# LilyPad-Dev-v34.net
KiCad netlist of a schematic drawn in EAGLE
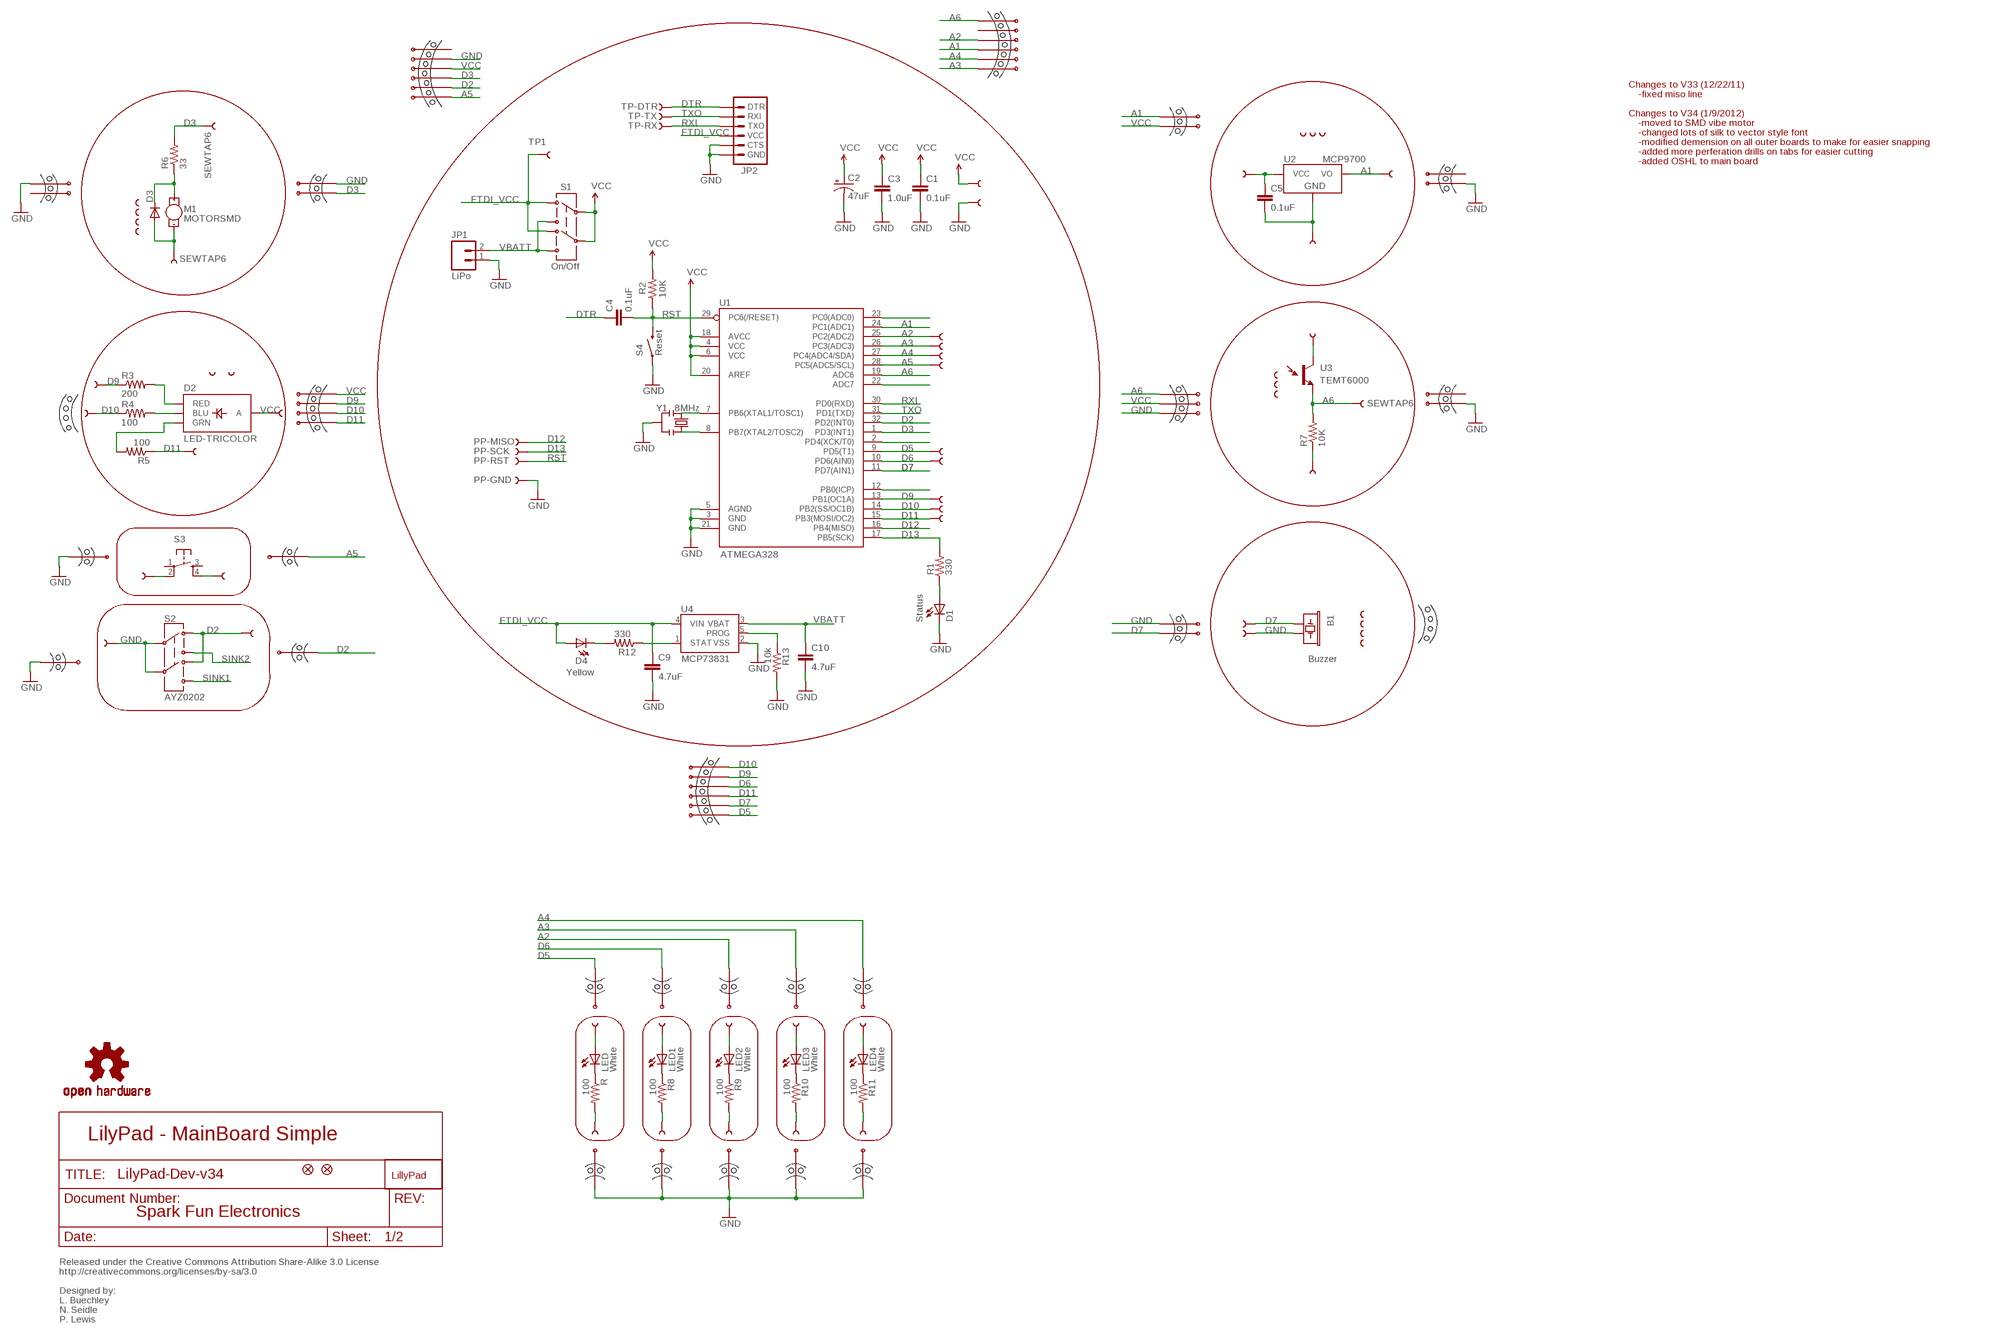
[diagram p0: schematic, sheet 1]
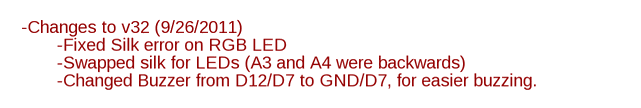
[diagram p1: schematic, sheet 2]

(export (version "E")
  (design (tool "Eeschema 10.0.6"))
  (components
    (comp (ref "1")
      (value "SEWTAP-NOHOLE2")
      (footprint "eagle-import:PETAL-NOHOLE-2SIDE")
      (libsource (lib "eagle-import") (part "SEWTAP-NOHOLE2"))
    )
    (comp (ref "2")
      (value "SEWTAP-NOHOLE2")
      (footprint "eagle-import:PETAL-NOHOLE-2SIDE")
      (libsource (lib "eagle-import") (part "SEWTAP-NOHOLE2"))
    )
    (comp (ref "3")
      (value "SEWTAP-NOHOLE2")
      (footprint "eagle-import:PETAL-NOHOLE-2SIDE")
      (libsource (lib "eagle-import") (part "SEWTAP-NOHOLE2"))
    )
    (comp (ref "4")
      (value "SEWTAP-NOHOLE2")
      (footprint "eagle-import:PETAL-NOHOLE-2SIDE")
      (libsource (lib "eagle-import") (part "SEWTAP-NOHOLE2"))
    )
    (comp (ref "A2/16")
      (value "SEWTAP9")
      (footprint "eagle-import:PETAL-LONG-1-2SIDE")
      (libsource (lib "eagle-import") (part "SEWTAP9"))
    )
    (comp (ref "A3/17")
      (value "SEWTAP9")
      (footprint "eagle-import:PETAL-LONG-1-2SIDE")
      (libsource (lib "eagle-import") (part "SEWTAP9"))
    )
    (comp (ref "A4/18")
      (value "SEWTAP9")
      (footprint "eagle-import:PETAL-LONG-1-2SIDE")
      (libsource (lib "eagle-import") (part "SEWTAP9"))
    )
    (comp (ref "A5/19")
      (value "SEWTAP9")
      (footprint "eagle-import:PETAL-LONG-1-2SIDE")
      (libsource (lib "eagle-import") (part "SEWTAP9"))
    )
    (comp (ref "B1")
      (value "Buzzer")
      (footprint "eagle-import:BUZZER-CCV")
      (libsource (lib "eagle-import") (part "BUZZERSMD2"))
    )
    (comp (ref "BUTTON-")
      (value "SEWTAP8")
      (footprint "eagle-import:PETAL-SMALL")
      (libsource (lib "eagle-import") (part "SEWTAP4"))
    )
    (comp (ref "BUTTONS")
      (value "SEWTAP8")
      (footprint "eagle-import:PETAL-SMALL")
      (libsource (lib "eagle-import") (part "SEWTAP4"))
    )
    (comp (ref "C1")
      (value "0.1uF")
      (footprint "eagle-import:0402-CAP")
      (libsource (lib "eagle-import") (part "CAP0402-CAP"))
    )
    (comp (ref "C2")
      (value "47uF")
      (footprint "eagle-import:EIA3528")
      (libsource (lib "eagle-import") (part "CAP_POL3528"))
    )
    (comp (ref "C3")
      (value "1.0uF")
      (footprint "eagle-import:0402-CAP")
      (libsource (lib "eagle-import") (part "CAP0402-CAP"))
    )
    (comp (ref "C4")
      (value "0.1uF")
      (footprint "eagle-import:0402-CAP")
      (libsource (lib "eagle-import") (part "CAP0402-CAP"))
    )
    (comp (ref "C5")
      (value "0.1uF")
      (footprint "eagle-import:0603-CAP")
      (libsource (lib "eagle-import") (part "CAP0603-CAP"))
    )
    (comp (ref "C9")
      (value "4.7uF")
      (footprint "eagle-import:0402-CAP")
      (libsource (lib "eagle-import") (part "CAP0402-CAP"))
    )
    (comp (ref "C10")
      (value "4.7uF")
      (footprint "eagle-import:0402-CAP")
      (libsource (lib "eagle-import") (part "CAP0402-CAP"))
    )
    (comp (ref "D1")
      (value "Status")
      (footprint "eagle-import:LED-0603")
      (libsource (lib "eagle-import") (part "LED0603"))
    )
    (comp (ref "D2")
      (value "LED-TRICOLOR")
      (footprint "eagle-import:LED-TRICOLOR-SMD")
      (libsource (lib "eagle-import") (part "LED-TRICOLOR"))
    )
    (comp (ref "D3")
      (value "DIODESOD")
      (footprint "eagle-import:SOD-323")
      (libsource (lib "eagle-import") (part "DIODESOD"))
    )
    (comp (ref "D4")
      (value "Yellow")
      (footprint "eagle-import:LED-0603")
      (libsource (lib "eagle-import") (part "LED0603"))
    )
    (comp (ref "JP1")
      (value "LiPo")
      (footprint "eagle-import:JST-2-SMD")
      (libsource (lib "eagle-import") (part "M02-JST-2MM-SMT"))
    )
    (comp (ref "JP2")
      (value "ARDUINO_SERIAL_PROGRAMSMD")
      (footprint "eagle-import:1X06-SMD")
      (libsource (lib "eagle-import") (part "ARDUINO_SERIAL_PROGRAMSMD"))
    )
    (comp (ref "JP3")
      (value "FIDUCIAL1X2")
      (footprint "eagle-import:FIDUCIAL-1X2")
      (libsource (lib "eagle-import") (part "FIDUCIAL1X2"))
    )
    (comp (ref "JP4")
      (value "FIDUCIAL1X2")
      (footprint "eagle-import:FIDUCIAL-1X2")
      (libsource (lib "eagle-import") (part "FIDUCIAL1X2"))
    )
    (comp (ref "LED")
      (value "White")
      (footprint "eagle-import:LED-1206")
      (libsource (lib "eagle-import") (part "SparkFun-3-2-07_LED1206"))
    )
    (comp (ref "LED+")
      (value "SEWTAP6")
      (footprint "eagle-import:PETAL-SMALL-2SIDE")
      (libsource (lib "eagle-import") (part "SEWTAP6"))
    )
    (comp (ref "LED+1")
      (value "SEWTAP6")
      (footprint "eagle-import:PETAL-SMALL-2SIDE")
      (libsource (lib "eagle-import") (part "SEWTAP6"))
    )
    (comp (ref "LED+2")
      (value "SEWTAP6")
      (footprint "eagle-import:PETAL-SMALL-2SIDE")
      (libsource (lib "eagle-import") (part "SEWTAP6"))
    )
    (comp (ref "LED+3")
      (value "SEWTAP6")
      (footprint "eagle-import:PETAL-SMALL-2SIDE")
      (libsource (lib "eagle-import") (part "SEWTAP6"))
    )
    (comp (ref "LED+4")
      (value "SEWTAP6")
      (footprint "eagle-import:PETAL-SMALL-2SIDE")
      (libsource (lib "eagle-import") (part "SEWTAP6"))
    )
    (comp (ref "LED-")
      (value "SEWTAP6")
      (footprint "eagle-import:PETAL-SMALL-2SIDE")
      (libsource (lib "eagle-import") (part "SEWTAP6"))
    )
    (comp (ref "LED-1")
      (value "SEWTAP6")
      (footprint "eagle-import:PETAL-SMALL-2SIDE")
      (libsource (lib "eagle-import") (part "SEWTAP6"))
    )
    (comp (ref "LED-2")
      (value "SEWTAP6")
      (footprint "eagle-import:PETAL-SMALL-2SIDE")
      (libsource (lib "eagle-import") (part "SEWTAP6"))
    )
    (comp (ref "LED-3")
      (value "SEWTAP6")
      (footprint "eagle-import:PETAL-SMALL-2SIDE")
      (libsource (lib "eagle-import") (part "SEWTAP6"))
    )
    (comp (ref "LED-4")
      (value "SEWTAP6")
      (footprint "eagle-import:PETAL-SMALL-2SIDE")
      (libsource (lib "eagle-import") (part "SEWTAP6"))
    )
    (comp (ref "LED1")
      (value "White")
      (footprint "eagle-import:LED-1206")
      (libsource (lib "eagle-import") (part "SparkFun-3-2-07_LED1206"))
    )
    (comp (ref "LED2")
      (value "White")
      (footprint "eagle-import:LED-1206")
      (libsource (lib "eagle-import") (part "SparkFun-3-2-07_LED1206"))
    )
    (comp (ref "LED3")
      (value "White")
      (footprint "eagle-import:LED-1206")
      (libsource (lib "eagle-import") (part "SparkFun-3-2-07_LED1206"))
    )
    (comp (ref "LED4")
      (value "White")
      (footprint "eagle-import:LED-1206")
      (libsource (lib "eagle-import") (part "SparkFun-3-2-07_LED1206"))
    )
    (comp (ref "LIGHT+")
      (value "SEWTAP6")
      (footprint "eagle-import:PETAL-SMALL")
      (libsource (lib "eagle-import") (part "SEWTAP4"))
    )
    (comp (ref "LIGHT-")
      (value "SEWTAP6")
      (footprint "eagle-import:PETAL-SMALL")
      (libsource (lib "eagle-import") (part "SEWTAP4"))
    )
    (comp (ref "LIGHT1")
      (value "SEWTAP-NOHOLE2")
      (footprint "eagle-import:PETAL-NOHOLE-2SIDE")
      (libsource (lib "eagle-import") (part "SEWTAP-NOHOLE2"))
    )
    (comp (ref "LIGHT2")
      (value "SEWTAP-NOHOLE2")
      (footprint "eagle-import:PETAL-NOHOLE-2SIDE")
      (libsource (lib "eagle-import") (part "SEWTAP-NOHOLE2"))
    )
    (comp (ref "LIGHT3")
      (value "SEWTAP-NOHOLE2")
      (footprint "eagle-import:PETAL-NOHOLE-2SIDE")
      (libsource (lib "eagle-import") (part "SEWTAP-NOHOLE2"))
    )
    (comp (ref "LIGHTS")
      (value "SEWTAP6")
      (footprint "eagle-import:PETAL-SMALL")
      (libsource (lib "eagle-import") (part "SEWTAP4"))
    )
    (comp (ref "LOGO")
      (value "LOGO-LPLPA")
      (footprint "eagle-import:LOGO-LPA")
      (libsource (lib "eagle-import") (part "LOGO-LPLPA"))
    )
    (comp (ref "M1")
      (value "MOTORSMD")
      (footprint "eagle-import:VIBE-MOTOR-10MM-SMD")
      (libsource (lib "eagle-import") (part "MOTORSMD"))
    )
    (comp (ref "PP-GND")
      (value "TEST-POINT3X5")
      (footprint "eagle-import:PAD.03X.05")
      (libsource (lib "eagle-import") (part "TEST-POINT3X5"))
    )
    (comp (ref "PP-MISO")
      (value "TEST-POINT3X5")
      (footprint "eagle-import:PAD.03X.05")
      (libsource (lib "eagle-import") (part "TEST-POINT3X5"))
    )
    (comp (ref "PP-RST")
      (value "TEST-POINT3X5")
      (footprint "eagle-import:PAD.03X.05")
      (libsource (lib "eagle-import") (part "TEST-POINT3X5"))
    )
    (comp (ref "PP-SCK")
      (value "TEST-POINT3X5")
      (footprint "eagle-import:PAD.03X.05")
      (libsource (lib "eagle-import") (part "TEST-POINT3X5"))
    )
    (comp (ref "R")
      (value "100")
      (footprint "eagle-import:0603-RES")
      (libsource (lib "eagle-import") (part "RESISTOR0603-RES"))
    )
    (comp (ref "R1")
      (value "330")
      (footprint "eagle-import:0402-RES")
      (libsource (lib "eagle-import") (part "RESISTOR0402-RES"))
    )
    (comp (ref "R2")
      (value "10K")
      (footprint "eagle-import:0402-RES")
      (libsource (lib "eagle-import") (part "RESISTOR0402-RES"))
    )
    (comp (ref "R3")
      (value "200")
      (footprint "eagle-import:0402-RES")
      (libsource (lib "eagle-import") (part "RESISTOR0402-RES"))
    )
    (comp (ref "R4")
      (value "100")
      (footprint "eagle-import:0402-RES")
      (libsource (lib "eagle-import") (part "RESISTOR0402-RES"))
    )
    (comp (ref "R5")
      (value "100")
      (footprint "eagle-import:0402-RES")
      (libsource (lib "eagle-import") (part "RESISTOR0402-RES"))
    )
    (comp (ref "R6")
      (value "33")
      (footprint "eagle-import:0402-RES")
      (libsource (lib "eagle-import") (part "RESISTOR0402-RES"))
    )
    (comp (ref "R7")
      (value "10K")
      (footprint "eagle-import:0402-RES")
      (libsource (lib "eagle-import") (part "RESISTOR0402-RES"))
    )
    (comp (ref "R8")
      (value "100")
      (footprint "eagle-import:0603-RES")
      (libsource (lib "eagle-import") (part "RESISTOR0603-RES"))
    )
    (comp (ref "R9")
      (value "100")
      (footprint "eagle-import:0603-RES")
      (libsource (lib "eagle-import") (part "RESISTOR0603-RES"))
    )
    (comp (ref "R10")
      (value "100")
      (footprint "eagle-import:0603-RES")
      (libsource (lib "eagle-import") (part "RESISTOR0603-RES"))
    )
    (comp (ref "R11")
      (value "100")
      (footprint "eagle-import:0603-RES")
      (libsource (lib "eagle-import") (part "RESISTOR0603-RES"))
    )
    (comp (ref "R12")
      (value "330")
      (footprint "eagle-import:0402-RES")
      (libsource (lib "eagle-import") (part "RESISTOR0402-RES"))
    )
    (comp (ref "R13")
      (value "10k")
      (footprint "eagle-import:0402-RES")
      (libsource (lib "eagle-import") (part "RESISTOR0402-RES"))
    )
    (comp (ref "S1")
      (value "On/Off")
      (footprint "eagle-import:AYZ0202")
      (libsource (lib "eagle-import") (part "AYZ0202"))
    )
    (comp (ref "S2")
      (value "AYZ0202")
      (footprint "eagle-import:AYZ0202")
      (libsource (lib "eagle-import") (part "AYZ0202"))
    )
    (comp (ref "S3")
      (value "TAC_SWITCHSMD")
      (footprint "eagle-import:TACTILE_SWITCH_SMD")
      (libsource (lib "eagle-import") (part "TAC_SWITCHSMD"))
    )
    (comp (ref "S4")
      (value "Reset")
      (footprint "eagle-import:TACTILE_SWITCH_SMD")
      (libsource (lib "eagle-import") (part "SWITCH-MOMENTARY-2SMD"))
    )
    (comp (ref "SLIDEOFF")
      (value "SEWTAP8")
      (footprint "eagle-import:PETAL-SMALL")
      (libsource (lib "eagle-import") (part "SEWTAP4"))
    )
    (comp (ref "SLIDEON")
      (value "SEWTAP8")
      (footprint "eagle-import:PETAL-SMALL")
      (libsource (lib "eagle-import") (part "SEWTAP4"))
    )
    (comp (ref "TEMP+")
      (value "SEWTAP6")
      (footprint "eagle-import:PETAL-SMALL")
      (libsource (lib "eagle-import") (part "SEWTAP4"))
    )
    (comp (ref "TEMP-")
      (value "SEWTAP6")
      (footprint "eagle-import:PETAL-SMALL")
      (libsource (lib "eagle-import") (part "SEWTAP4"))
    )
    (comp (ref "TEMP1")
      (value "SEWTAP-NOHOLE2")
      (footprint "eagle-import:PETAL-NOHOLE-2SIDE")
      (libsource (lib "eagle-import") (part "SEWTAP-NOHOLE2"))
    )
    (comp (ref "TEMP2")
      (value "SEWTAP-NOHOLE2")
      (footprint "eagle-import:PETAL-NOHOLE-2SIDE")
      (libsource (lib "eagle-import") (part "SEWTAP-NOHOLE2"))
    )
    (comp (ref "TEMP3")
      (value "SEWTAP-NOHOLE2")
      (footprint "eagle-import:PETAL-NOHOLE-2SIDE")
      (libsource (lib "eagle-import") (part "SEWTAP-NOHOLE2"))
    )
    (comp (ref "TEMPS")
      (value "SEWTAP6")
      (footprint "eagle-import:PETAL-SMALL")
      (libsource (lib "eagle-import") (part "SEWTAP4"))
    )
    (comp (ref "TP-DTR")
      (value "TEST-POINT3X5")
      (footprint "eagle-import:PAD.03X.05")
      (libsource (lib "eagle-import") (part "TEST-POINT3X5"))
    )
    (comp (ref "TP-RX")
      (value "TEST-POINT3X5")
      (footprint "eagle-import:PAD.03X.05")
      (libsource (lib "eagle-import") (part "TEST-POINT3X5"))
    )
    (comp (ref "TP-TX")
      (value "TEST-POINT3X5")
      (footprint "eagle-import:PAD.03X.05")
      (libsource (lib "eagle-import") (part "TEST-POINT3X5"))
    )
    (comp (ref "TP1")
      (value "TEST-POINT3X5")
      (footprint "eagle-import:PAD.03X.05")
      (libsource (lib "eagle-import") (part "TEST-POINT3X5"))
    )
    (comp (ref "U$1")
      (value "SEWTAP9")
      (footprint "eagle-import:PETAL-LONG-1-2SIDE")
      (libsource (lib "eagle-import") (part "SEWTAP9"))
    )
    (comp (ref "U$2")
      (value "MOUSE-BITE-2")
      (footprint "eagle-import:MOUSE-BITE-2")
      (libsource (lib "eagle-import") (part "MOUSE-BITE-2"))
    )
    (comp (ref "U$3")
      (value "MOUSE-BITE-2")
      (footprint "eagle-import:MOUSE-BITE-2")
      (libsource (lib "eagle-import") (part "MOUSE-BITE-2"))
    )
    (comp (ref "U$4")
      (value "SEWTAP9")
      (footprint "eagle-import:PETAL-LONG-1-2SIDE")
      (libsource (lib "eagle-import") (part "SEWTAP9"))
    )
    (comp (ref "U$5")
      (value "MOUSE-BITE-2")
      (footprint "eagle-import:MOUSE-BITE-2")
      (libsource (lib "eagle-import") (part "MOUSE-BITE-2"))
    )
    (comp (ref "U$6")
      (value "MOUSE-BITE-2")
      (footprint "eagle-import:MOUSE-BITE-2")
      (libsource (lib "eagle-import") (part "MOUSE-BITE-2"))
    )
    (comp (ref "U$7")
      (value "MOUSE-BITE-66")
      (footprint "eagle-import:MOUSE-BITE-6")
      (libsource (lib "eagle-import") (part "MOUSE-BITE-66"))
    )
    (comp (ref "U$8")
      (value "MOUSE-BITE-66")
      (footprint "eagle-import:MOUSE-BITE-6")
      (libsource (lib "eagle-import") (part "MOUSE-BITE-66"))
    )
    (comp (ref "U$10")
      (value "MOUSE-BITE-12_HOLES")
      (footprint "eagle-import:MOUST-BITE-1-(2_HOLES)")
      (libsource (lib "eagle-import") (part "MOUSE-BITE-12_HOLES"))
    )
    (comp (ref "U$11")
      (value "MOUSE-BITE-12_HOLES")
      (footprint "eagle-import:MOUST-BITE-1-(2_HOLES)")
      (libsource (lib "eagle-import") (part "MOUSE-BITE-12_HOLES"))
    )
    (comp (ref "U$12")
      (value "MOUSE-BITE-12_HOLES")
      (footprint "eagle-import:MOUST-BITE-1-(2_HOLES)")
      (libsource (lib "eagle-import") (part "MOUSE-BITE-12_HOLES"))
    )
    (comp (ref "U$13")
      (value "MOUSE-BITE-12_HOLES")
      (footprint "eagle-import:MOUST-BITE-1-(2_HOLES)")
      (libsource (lib "eagle-import") (part "MOUSE-BITE-12_HOLES"))
    )
    (comp (ref "U$14")
      (value "MOUSE-BITE-12_HOLES")
      (footprint "eagle-import:MOUST-BITE-1-(2_HOLES)")
      (libsource (lib "eagle-import") (part "MOUSE-BITE-12_HOLES"))
    )
    (comp (ref "U$15")
      (value "MOUSE-BITE-12_HOLES")
      (footprint "eagle-import:MOUST-BITE-1-(2_HOLES)")
      (libsource (lib "eagle-import") (part "MOUSE-BITE-12_HOLES"))
    )
    (comp (ref "U$16")
      (value "MOUSE-BITE-12_HOLES")
      (footprint "eagle-import:MOUST-BITE-1-(2_HOLES)")
      (libsource (lib "eagle-import") (part "MOUSE-BITE-12_HOLES"))
    )
    (comp (ref "U$17")
      (value "MOUSE-BITE-12_HOLES")
      (footprint "eagle-import:MOUST-BITE-1-(2_HOLES)")
      (libsource (lib "eagle-import") (part "MOUSE-BITE-12_HOLES"))
    )
    (comp (ref "U$18")
      (value "MOUSE-BITE-12_HOLES")
      (footprint "eagle-import:MOUST-BITE-1-(2_HOLES)")
      (libsource (lib "eagle-import") (part "MOUSE-BITE-12_HOLES"))
    )
    (comp (ref "U$19")
      (value "MOUSE-BITE-12_HOLES")
      (footprint "eagle-import:MOUST-BITE-1-(2_HOLES)")
      (libsource (lib "eagle-import") (part "MOUSE-BITE-12_HOLES"))
    )
    (comp (ref "U$20")
      (value "MOUSE-BITE-4")
      (footprint "eagle-import:MOUSE-BITE-4")
      (libsource (lib "eagle-import") (part "MOUSE-BITE-4"))
    )
    (comp (ref "U$22")
      (value "SEWTAP6")
      (footprint "eagle-import:PETAL-SMALL-2SIDE")
      (libsource (lib "eagle-import") (part "SEWTAP6"))
    )
    (comp (ref "U$23")
      (value "SEWTAP6")
      (footprint "eagle-import:PETAL-SMALL-2SIDE")
      (libsource (lib "eagle-import") (part "SEWTAP6"))
    )
    (comp (ref "U$24")
      (value "SEWTAP6")
      (footprint "eagle-import:PETAL-SMALL-2SIDE")
      (libsource (lib "eagle-import") (part "SEWTAP6"))
    )
    (comp (ref "U$25")
      (value "SEWTAP6")
      (footprint "eagle-import:PETAL-SMALL-2SIDE")
      (libsource (lib "eagle-import") (part "SEWTAP6"))
    )
    (comp (ref "U$26")
      (value "SEWTAP-NOHOLE2")
      (footprint "eagle-import:PETAL-NOHOLE-2SIDE")
      (libsource (lib "eagle-import") (part "SEWTAP-NOHOLE2"))
    )
    (comp (ref "U$27")
      (value "SEWTAP-NOHOLE2")
      (footprint "eagle-import:PETAL-NOHOLE-2SIDE")
      (libsource (lib "eagle-import") (part "SEWTAP-NOHOLE2"))
    )
    (comp (ref "U$32")
      (value "MOUSE-BITE-2")
      (footprint "eagle-import:MOUSE-BITE-2")
      (libsource (lib "eagle-import") (part "MOUSE-BITE-2"))
    )
    (comp (ref "U$32-")
      (value "SEWTAP6")
      (footprint "eagle-import:PETAL-SMALL")
      (libsource (lib "eagle-import") (part "SEWTAP4"))
    )
    (comp (ref "U$33")
      (value "MOUSE-BITE-3")
      (footprint "eagle-import:MOUSE-BITE-3")
      (libsource (lib "eagle-import") (part "MOUSE-BITE-3"))
    )
    (comp (ref "U$33+")
      (value "SEWTAP6")
      (footprint "eagle-import:PETAL-SMALL")
      (libsource (lib "eagle-import") (part "SEWTAP4"))
    )
    (comp (ref "U$37")
      (value "SEWTAP9")
      (footprint "eagle-import:PETAL-LONG-1-2SIDE")
      (libsource (lib "eagle-import") (part "SEWTAP9"))
    )
    (comp (ref "U$39")
      (value "SEWTAP9")
      (footprint "eagle-import:PETAL-LONG-1-2SIDE")
      (libsource (lib "eagle-import") (part "SEWTAP9"))
    )
    (comp (ref "U$40")
      (value "MOUSE-BITE-12_HOLES")
      (footprint "eagle-import:MOUST-BITE-1-(2_HOLES)")
      (libsource (lib "eagle-import") (part "MOUSE-BITE-12_HOLES"))
    )
    (comp (ref "U$41")
      (value "SEWTAP9")
      (footprint "eagle-import:PETAL-LONG-1-2SIDE")
      (libsource (lib "eagle-import") (part "SEWTAP9"))
    )
    (comp (ref "U$42")
      (value "MOUSE-BITE-12_HOLES")
      (footprint "eagle-import:MOUST-BITE-1-(2_HOLES)")
      (libsource (lib "eagle-import") (part "MOUSE-BITE-12_HOLES"))
    )
    (comp (ref "U$43")
      (value "SEWTAP9")
      (footprint "eagle-import:PETAL-LONG-1-2SIDE")
      (libsource (lib "eagle-import") (part "SEWTAP9"))
    )
    (comp (ref "U$44")
      (value "MOUSE-BITE-12_HOLES")
      (footprint "eagle-import:MOUST-BITE-1-(2_HOLES)")
      (libsource (lib "eagle-import") (part "MOUSE-BITE-12_HOLES"))
    )
    (comp (ref "U$45")
      (value "SEWTAP9")
      (footprint "eagle-import:PETAL-LONG-1-2SIDE")
      (libsource (lib "eagle-import") (part "SEWTAP9"))
    )
    (comp (ref "U$46")
      (value "MOUSE-BITE-12_HOLES")
      (footprint "eagle-import:MOUST-BITE-1-(2_HOLES)")
      (libsource (lib "eagle-import") (part "MOUSE-BITE-12_HOLES"))
    )
    (comp (ref "U$47")
      (value "MOUSE-BITE-2")
      (footprint "eagle-import:MOUSE-BITE-2")
      (libsource (lib "eagle-import") (part "MOUSE-BITE-2"))
    )
    (comp (ref "U$48")
      (value "MOUSE-BITE-3(NO_PADS)")
      (footprint "eagle-import:MOUSE-BITE-3(NO_PADS)")
      (libsource (lib "eagle-import") (part "MOUSE-BITE-3(NO_PADS)"))
    )
    (comp (ref "U$49")
      (value "MOUSE-BITE-3(NO_PADS)")
      (footprint "eagle-import:MOUSE-BITE-3(NO_PADS)")
      (libsource (lib "eagle-import") (part "MOUSE-BITE-3(NO_PADS)"))
    )
    (comp (ref "U$51")
      (value "MOUSE-BITE-66")
      (footprint "eagle-import:MOUSE-BITE-6")
      (libsource (lib "eagle-import") (part "MOUSE-BITE-66"))
    )
    (comp (ref "U$52")
      (value "OSHW-LOGOS")
      (footprint "eagle-import:OSHW-LOGO-S")
      (libsource (lib "eagle-import") (part "OSHW-LOGOS"))
    )
    (comp (ref "U1")
      (value "ATMEGA328")
      (footprint "eagle-import:TQFP32-08")
      (libsource (lib "eagle-import") (part "ATMEGA168"))
    )
    (comp (ref "U2")
      (value "MCP9700")
      (footprint "eagle-import:SOT23-3")
      (libsource (lib "eagle-import") (part "MCP9700SMD"))
    )
    (comp (ref "U3")
      (value "TEMT6000")
      (footprint "eagle-import:TEMT6000-SEN")
      (libsource (lib "eagle-import") (part "TEMT6000"))
    )
    (comp (ref "U4")
      (value "MCP73831")
      (footprint "eagle-import:SOT23-5")
      (libsource (lib "eagle-import") (part "MCP73831"))
    )
    (comp (ref "VIBE+")
      (value "SEWTAP6")
      (footprint "eagle-import:PETAL-SMALL")
      (libsource (lib "eagle-import") (part "SEWTAP4"))
    )
    (comp (ref "VIBE-")
      (value "SEWTAP6")
      (footprint "eagle-import:PETAL-SMALL")
      (libsource (lib "eagle-import") (part "SEWTAP4"))
    )
    (comp (ref "VIBE1")
      (value "SEWTAP-NOHOLE2")
      (footprint "eagle-import:PETAL-NOHOLE-2SIDE")
      (libsource (lib "eagle-import") (part "SEWTAP-NOHOLE2"))
    )
    (comp (ref "VIBE2")
      (value "SEWTAP-NOHOLE2")
      (footprint "eagle-import:PETAL-NOHOLE-2SIDE")
      (libsource (lib "eagle-import") (part "SEWTAP-NOHOLE2"))
    )
    (comp (ref "VIBE3")
      (value "SEWTAP-NOHOLE2")
      (footprint "eagle-import:PETAL-NOHOLE-2SIDE")
      (libsource (lib "eagle-import") (part "SEWTAP-NOHOLE2"))
    )
    (comp (ref "VIBE4")
      (value "SEWTAP-NOHOLE2")
      (footprint "eagle-import:PETAL-NOHOLE-2SIDE")
      (libsource (lib "eagle-import") (part "SEWTAP-NOHOLE2"))
    )
    (comp (ref "Y1")
      (value "8MHz")
      (footprint "eagle-import:RESONATOR-SMD")
      (libsource (lib "eagle-import") (part "RESONATORSMD"))
    )
  )
  (nets
    (net (code "1") (name "A1") (class "Default")
      (node (ref "TEMPS") (pin "1") (pinfunction "1_1") (pintype "bidirectional"))
      (node (ref "U$2") (pin "P$1") (pinfunction "P$1_P$1") (pintype "bidirectional"))
      (node (ref "U$7") (pin "P$4") (pinfunction "P$4_P$4") (pintype "bidirectional"))
      (node (ref "U1") (pin "24") (pinfunction "PC1(ADC1)_24") (pintype "bidirectional"))
      (node (ref "U2") (pin "2") (pinfunction "VO_2") (pintype "bidirectional"))
    )
    (net (code "2") (name "A2") (class "Default")
      (node (ref "A2/16") (pin "1") (pinfunction "1_1") (pintype "bidirectional"))
      (node (ref "U$12") (pin "P$1") (pinfunction "P$1_P$1") (pintype "bidirectional"))
      (node (ref "U$7") (pin "P$3") (pinfunction "P$3_P$3") (pintype "bidirectional"))
      (node (ref "U1") (pin "25") (pinfunction "PC2(ADC2)_25") (pintype "bidirectional"))
    )
    (net (code "3") (name "A3") (class "Default")
      (node (ref "A3/17") (pin "1") (pinfunction "1_1") (pintype "bidirectional"))
      (node (ref "U$13") (pin "P$1") (pinfunction "P$1_P$1") (pintype "bidirectional"))
      (node (ref "U$7") (pin "P$6") (pinfunction "P$6_P$6") (pintype "bidirectional"))
      (node (ref "U1") (pin "26") (pinfunction "PC3(ADC3)_26") (pintype "bidirectional"))
    )
    (net (code "4") (name "A4") (class "Default")
      (node (ref "A4/18") (pin "1") (pinfunction "1_1") (pintype "bidirectional"))
      (node (ref "U$14") (pin "P$1") (pinfunction "P$1_P$1") (pintype "bidirectional"))
      (node (ref "U$7") (pin "P$5") (pinfunction "P$5_P$5") (pintype "bidirectional"))
      (node (ref "U1") (pin "27") (pinfunction "PC4(ADC4/SDA)_27") (pintype "bidirectional"))
    )
    (net (code "5") (name "A5") (class "Default")
      (node (ref "A5/19") (pin "1") (pinfunction "1_1") (pintype "bidirectional"))
      (node (ref "BUTTONS") (pin "1") (pinfunction "1_1") (pintype "bidirectional"))
      (node (ref "S3") (pin "2") (pinfunction "2_2") (pintype "passive"))
      (node (ref "U$40") (pin "P$1") (pinfunction "P$1_P$1") (pintype "bidirectional"))
      (node (ref "U$8") (pin "P$1") (pinfunction "P$1_P$1") (pintype "bidirectional"))
      (node (ref "U1") (pin "28") (pinfunction "PC5(ADC5/SCL)_28") (pintype "bidirectional"))
    )
    (net (code "6") (name "A6") (class "Default")
      (node (ref "LIGHTS") (pin "1") (pinfunction "1_1") (pintype "bidirectional"))
      (node (ref "R7") (pin "2") (pinfunction "2_2") (pintype "passive"))
      (node (ref "U$33") (pin "P$1") (pinfunction "P$1_P$1") (pintype "bidirectional"))
      (node (ref "U$7") (pin "P$1") (pinfunction "P$1_P$1") (pintype "bidirectional"))
      (node (ref "U1") (pin "19") (pinfunction "ADC6_19") (pintype "bidirectional"))
      (node (ref "U3") (pin "EMITTER") (pinfunction "E1_EMITTER") (pintype "passive"))
    )
    (net (code "7") (name "D2") (class "Default")
      (node (ref "S2") (pin "3") (pinfunction "1_3") (pintype "bidirectional"))
      (node (ref "S2") (pin "6") (pinfunction "4_6") (pintype "bidirectional"))
      (node (ref "SLIDEON") (pin "1") (pinfunction "1_1") (pintype "bidirectional"))
      (node (ref "U$46") (pin "P$1") (pinfunction "P$1_P$1") (pintype "bidirectional"))
      (node (ref "U$8") (pin "P$2") (pinfunction "P$2_P$2") (pintype "bidirectional"))
      (node (ref "U1") (pin "32") (pinfunction "PD2(INT0)_32") (pintype "bidirectional"))
    )
    (net (code "8") (name "D3") (class "Default")
      (node (ref "R6") (pin "2") (pinfunction "2_2") (pintype "passive"))
      (node (ref "U$5") (pin "P$1") (pinfunction "P$1_P$1") (pintype "bidirectional"))
      (node (ref "U$8") (pin "P$3") (pinfunction "P$3_P$3") (pintype "bidirectional"))
      (node (ref "U1") (pin "1") (pinfunction "PD3(INT1)_1") (pintype "bidirectional"))
      (node (ref "VIBE+") (pin "1") (pinfunction "1_1") (pintype "bidirectional"))
    )
    (net (code "9") (name "D5") (class "Default")
      (node (ref "U$10") (pin "P$1") (pinfunction "P$1_P$1") (pintype "bidirectional"))
      (node (ref "U$41") (pin "1") (pinfunction "1_1") (pintype "bidirectional"))
      (node (ref "U$51") (pin "P$1") (pinfunction "P$1_P$1") (pintype "bidirectional"))
      (node (ref "U1") (pin "9") (pinfunction "PD5(T1)_9") (pintype "bidirectional"))
    )
    (net (code "10") (name "D6") (class "Default")
      (node (ref "U$1") (pin "1") (pinfunction "1_1") (pintype "bidirectional"))
      (node (ref "U$11") (pin "P$1") (pinfunction "P$1_P$1") (pintype "bidirectional"))
      (node (ref "U$51") (pin "P$4") (pinfunction "P$4_P$4") (pintype "bidirectional"))
      (node (ref "U1") (pin "10") (pinfunction "PD6(AIN0)_10") (pintype "bidirectional"))
    )
    (net (code "11") (name "D7") (class "Default")
      (node (ref "B1") (pin "+") (pinfunction "1_+") (pintype "passive"))
      (node (ref "U$32") (pin "P$2") (pinfunction "P$2_P$2") (pintype "bidirectional"))
      (node (ref "U$33+") (pin "1") (pinfunction "1_1") (pintype "bidirectional"))
      (node (ref "U$51") (pin "P$2") (pinfunction "P$2_P$2") (pintype "bidirectional"))
      (node (ref "U1") (pin "11") (pinfunction "PD7(AIN1)_11") (pintype "bidirectional"))
    )
    (net (code "12") (name "D9") (class "Default")
      (node (ref "R3") (pin "1") (pinfunction "1_1") (pintype "passive"))
      (node (ref "U$20") (pin "P$3") (pinfunction "P$3_P$3") (pintype "bidirectional"))
      (node (ref "U$22") (pin "1") (pinfunction "1_1") (pintype "bidirectional"))
      (node (ref "U$37") (pin "1") (pinfunction "1_1") (pintype "bidirectional"))
      (node (ref "U$51") (pin "P$5") (pinfunction "P$5_P$5") (pintype "bidirectional"))
      (node (ref "U1") (pin "13") (pinfunction "PB1(OC1A)_13") (pintype "bidirectional"))
    )
    (net (code "13") (name "D10") (class "Default")
      (node (ref "R4") (pin "1") (pinfunction "1_1") (pintype "passive"))
      (node (ref "U$20") (pin "P$2") (pinfunction "P$2_P$2") (pintype "bidirectional"))
      (node (ref "U$24") (pin "1") (pinfunction "1_1") (pintype "bidirectional"))
      (node (ref "U$39") (pin "1") (pinfunction "1_1") (pintype "bidirectional"))
      (node (ref "U$51") (pin "P$6") (pinfunction "P$6_P$6") (pintype "bidirectional"))
      (node (ref "U1") (pin "14") (pinfunction "PB2(SS/OC1B)_14") (pintype "bidirectional"))
    )
    (net (code "14") (name "D11") (class "Default")
      (node (ref "R5") (pin "1") (pinfunction "1_1") (pintype "passive"))
      (node (ref "U$20") (pin "P$1") (pinfunction "P$1_P$1") (pintype "bidirectional"))
      (node (ref "U$23") (pin "1") (pinfunction "1_1") (pintype "bidirectional"))
      (node (ref "U$4") (pin "1") (pinfunction "1_1") (pintype "bidirectional"))
      (node (ref "U$51") (pin "P$3") (pinfunction "P$3_P$3") (pintype "bidirectional"))
      (node (ref "U1") (pin "15") (pinfunction "PB3(MOSI/OC2)_15") (pintype "bidirectional"))
    )
    (net (code "15") (name "D12") (class "Default")
      (node (ref "PP-MISO") (pin "P$1") (pinfunction "1_P$1") (pintype "bidirectional"))
      (node (ref "U1") (pin "16") (pinfunction "PB4(MISO)_16") (pintype "bidirectional"))
    )
    (net (code "16") (name "D13") (class "Default")
      (node (ref "PP-SCK") (pin "P$1") (pinfunction "1_P$1") (pintype "bidirectional"))
      (node (ref "R1") (pin "2") (pinfunction "2_2") (pintype "passive"))
      (node (ref "U1") (pin "17") (pinfunction "PB5(SCK)_17") (pintype "bidirectional"))
    )
    (net (code "17") (name "DTR") (class "Default")
      (node (ref "C4") (pin "1") (pinfunction "1_1") (pintype "passive"))
      (node (ref "JP2") (pin "1") (pinfunction "DTR_1") (pintype "passive"))
      (node (ref "TP-DTR") (pin "P$1") (pinfunction "1_P$1") (pintype "bidirectional"))
    )
    (net (code "18") (name "FTDI_VCC") (class "Default")
      (node (ref "C9") (pin "1") (pinfunction "1_1") (pintype "passive"))
      (node (ref "D4") (pin "A") (pinfunction "A_A") (pintype "passive"))
      (node (ref "JP2") (pin "4") (pinfunction "VCC_4") (pintype "passive"))
      (node (ref "S1") (pin "3") (pinfunction "1_3") (pintype "bidirectional"))
      (node (ref "S1") (pin "6") (pinfunction "4_6") (pintype "bidirectional"))
      (node (ref "TP1") (pin "P$1") (pinfunction "1_P$1") (pintype "bidirectional"))
      (node (ref "U4") (pin "4") (pinfunction "VIN_4") (pintype "power_in"))
    )
    (net (code "19") (name "GND") (class "Default")
      (node (ref "B1") (pin "-") (pinfunction "2_-") (pintype "passive"))
      (node (ref "BUTTON-") (pin "1") (pinfunction "1_1") (pintype "bidirectional"))
      (node (ref "C1") (pin "2") (pinfunction "2_2") (pintype "passive"))
      (node (ref "C10") (pin "2") (pinfunction "2_2") (pintype "passive"))
      (node (ref "C2") (pin "C") (pinfunction "-_C") (pintype "passive"))
      (node (ref "C3") (pin "2") (pinfunction "2_2") (pintype "passive"))
      (node (ref "C5") (pin "2") (pinfunction "2_2") (pintype "passive"))
      (node (ref "C9") (pin "2") (pinfunction "2_2") (pintype "passive"))
      (node (ref "D1") (pin "C") (pinfunction "C_C") (pintype "passive"))
      (node (ref "D3") (pin "2") (pinfunction "A_2") (pintype "passive"))
      (node (ref "JP1") (pin "1") (pinfunction "1_1") (pintype "passive"))
      (node (ref "JP2") (pin "5") (pinfunction "CTS_5") (pintype "passive"))
      (node (ref "JP2") (pin "6") (pinfunction "GND_6") (pintype "passive"))
      (node (ref "LIGHT-") (pin "1") (pinfunction "1_1") (pintype "bidirectional"))
      (node (ref "M1") (pin "P$2") (pinfunction "-_P$2") (pintype "bidirectional"))
      (node (ref "PP-GND") (pin "P$1") (pinfunction "1_P$1") (pintype "bidirectional"))
      (node (ref "R13") (pin "2") (pinfunction "2_2") (pintype "passive"))
      (node (ref "R7") (pin "1") (pinfunction "1_1") (pintype "passive"))
      (node (ref "S2") (pin "2") (pinfunction "2_2") (pintype "bidirectional"))
      (node (ref "S2") (pin "5") (pinfunction "5_5") (pintype "bidirectional"))
      (node (ref "S3") (pin "4") (pinfunction "4_4") (pintype "passive"))
      (node (ref "S4") (pin "1") (pinfunction "1_1") (pintype "passive"))
      (node (ref "SLIDEOFF") (pin "1") (pinfunction "1_1") (pintype "bidirectional"))
      (node (ref "TEMP-") (pin "1") (pinfunction "1_1") (pintype "bidirectional"))
      (node (ref "U$15") (pin "P$1") (pinfunction "P$1_P$1") (pintype "bidirectional"))
      (node (ref "U$16") (pin "P$1") (pinfunction "P$1_P$1") (pintype "bidirectional"))
      (node (ref "U$17") (pin "P$1") (pinfunction "P$1_P$1") (pintype "bidirectional"))
      (node (ref "U$18") (pin "P$1") (pinfunction "P$1_P$1") (pintype "bidirectional"))
      (node (ref "U$19") (pin "P$1") (pinfunction "P$1_P$1") (pintype "bidirectional"))
      (node (ref "U$3") (pin "P$1") (pinfunction "P$1_P$1") (pintype "bidirectional"))
      (node (ref "U$32") (pin "P$1") (pinfunction "P$1_P$1") (pintype "bidirectional"))
      (node (ref "U$32-") (pin "1") (pinfunction "1_1") (pintype "bidirectional"))
      (node (ref "U$33") (pin "P$3") (pinfunction "P$3_P$3") (pintype "bidirectional"))
      (node (ref "U$42") (pin "P$1") (pinfunction "P$1_P$1") (pintype "bidirectional"))
      (node (ref "U$43") (pin "1") (pinfunction "1_1") (pintype "bidirectional"))
      (node (ref "U$44") (pin "P$1") (pinfunction "P$1_P$1") (pintype "bidirectional"))
      (node (ref "U$47") (pin "P$1") (pinfunction "P$1_P$1") (pintype "bidirectional"))
      (node (ref "U$5") (pin "P$2") (pinfunction "P$2_P$2") (pintype "bidirectional"))
      (node (ref "U$6") (pin "P$1") (pinfunction "P$1_P$1") (pintype "bidirectional"))
      (node (ref "U$8") (pin "P$5") (pinfunction "P$5_P$5") (pintype "bidirectional"))
      (node (ref "U1") (pin "21") (pinfunction "GND_21") (pintype "bidirectional"))
      (node (ref "U1") (pin "3") (pinfunction "GND_3") (pintype "bidirectional"))
      (node (ref "U1") (pin "5") (pinfunction "AGND_5") (pintype "bidirectional"))
      (node (ref "U2") (pin "3") (pinfunction "GND_3") (pintype "bidirectional"))
      (node (ref "U4") (pin "2") (pinfunction "VSS_2") (pintype "power_in"))
      (node (ref "VIBE-") (pin "1") (pinfunction "1_1") (pintype "bidirectional"))
      (node (ref "Y1") (pin "2") (pinfunction "2_2") (pintype "passive"))
    )
    (net (code "20") (name "Net-(D1-PadA)") (class "Default")
      (node (ref "D1") (pin "A") (pinfunction "A_A") (pintype "passive"))
      (node (ref "R1") (pin "1") (pinfunction "1_1") (pintype "passive"))
    )
    (net (code "21") (name "Net-(D2-BLU)") (class "Default")
      (node (ref "D2") (pin "B") (pinfunction "BLU_B") (pintype "bidirectional"))
      (node (ref "R4") (pin "2") (pinfunction "2_2") (pintype "passive"))
    )
    (net (code "22") (name "Net-(D2-GRN)") (class "Default")
      (node (ref "D2") (pin "G") (pinfunction "GRN_G") (pintype "bidirectional"))
      (node (ref "R5") (pin "2") (pinfunction "2_2") (pintype "passive"))
    )
    (net (code "23") (name "Net-(D2-RED)") (class "Default")
      (node (ref "D2") (pin "R") (pinfunction "RED_R") (pintype "bidirectional"))
      (node (ref "R3") (pin "2") (pinfunction "2_2") (pintype "passive"))
    )
    (net (code "24") (name "Net-(D3-C)") (class "Default")
      (node (ref "D3") (pin "1") (pinfunction "C_1") (pintype "passive"))
      (node (ref "M1") (pin "P$1") (pinfunction "+_P$1") (pintype "bidirectional"))
      (node (ref "R6") (pin "1") (pinfunction "1_1") (pintype "passive"))
    )
    (net (code "25") (name "Net-(D4-PadC)") (class "Default")
      (node (ref "D4") (pin "C") (pinfunction "C_C") (pintype "passive"))
      (node (ref "R12") (pin "2") (pinfunction "2_2") (pintype "passive"))
    )
    (net (code "26") (name "Net-(LED+-Pad1)") (class "Default")
      (node (ref "LED") (pin "A") (pinfunction "A_A") (pintype "passive"))
      (node (ref "LED+") (pin "1") (pinfunction "1_1") (pintype "bidirectional"))
    )
    (net (code "27") (name "Net-(LED+1-Pad1)") (class "Default")
      (node (ref "LED+1") (pin "1") (pinfunction "1_1") (pintype "bidirectional"))
      (node (ref "LED1") (pin "A") (pinfunction "A_A") (pintype "passive"))
    )
    (net (code "28") (name "Net-(LED+2-Pad1)") (class "Default")
      (node (ref "LED+2") (pin "1") (pinfunction "1_1") (pintype "bidirectional"))
      (node (ref "LED2") (pin "A") (pinfunction "A_A") (pintype "passive"))
    )
    (net (code "29") (name "Net-(LED+3-Pad1)") (class "Default")
      (node (ref "LED+3") (pin "1") (pinfunction "1_1") (pintype "bidirectional"))
      (node (ref "LED3") (pin "A") (pinfunction "A_A") (pintype "passive"))
    )
    (net (code "30") (name "Net-(LED+4-Pad1)") (class "Default")
      (node (ref "LED+4") (pin "1") (pinfunction "1_1") (pintype "bidirectional"))
      (node (ref "LED4") (pin "A") (pinfunction "A_A") (pintype "passive"))
    )
    (net (code "31") (name "Net-(LED--Pad1)") (class "Default")
      (node (ref "LED-") (pin "1") (pinfunction "1_1") (pintype "bidirectional"))
      (node (ref "R") (pin "2") (pinfunction "2_2") (pintype "passive"))
    )
    (net (code "32") (name "Net-(LED-1-Pad1)") (class "Default")
      (node (ref "LED-1") (pin "1") (pinfunction "1_1") (pintype "bidirectional"))
      (node (ref "R8") (pin "2") (pinfunction "2_2") (pintype "passive"))
    )
    (net (code "33") (name "Net-(LED-2-Pad1)") (class "Default")
      (node (ref "LED-2") (pin "1") (pinfunction "1_1") (pintype "bidirectional"))
      (node (ref "R9") (pin "2") (pinfunction "2_2") (pintype "passive"))
    )
    (net (code "34") (name "Net-(LED-3-Pad1)") (class "Default")
      (node (ref "LED-3") (pin "1") (pinfunction "1_1") (pintype "bidirectional"))
      (node (ref "R10") (pin "2") (pinfunction "2_2") (pintype "passive"))
    )
    (net (code "35") (name "Net-(LED-4-Pad1)") (class "Default")
      (node (ref "LED-4") (pin "1") (pinfunction "1_1") (pintype "bidirectional"))
      (node (ref "R11") (pin "2") (pinfunction "2_2") (pintype "passive"))
    )
    (net (code "36") (name "Net-(LED-PadC)") (class "Default")
      (node (ref "LED") (pin "C") (pinfunction "C_C") (pintype "passive"))
      (node (ref "R") (pin "1") (pinfunction "1_1") (pintype "passive"))
    )
    (net (code "37") (name "Net-(LED1-PadC)") (class "Default")
      (node (ref "LED1") (pin "C") (pinfunction "C_C") (pintype "passive"))
      (node (ref "R8") (pin "1") (pinfunction "1_1") (pintype "passive"))
    )
    (net (code "38") (name "Net-(LED2-PadC)") (class "Default")
      (node (ref "LED2") (pin "C") (pinfunction "C_C") (pintype "passive"))
      (node (ref "R9") (pin "1") (pinfunction "1_1") (pintype "passive"))
    )
    (net (code "39") (name "Net-(LED3-PadC)") (class "Default")
      (node (ref "LED3") (pin "C") (pinfunction "C_C") (pintype "passive"))
      (node (ref "R10") (pin "1") (pinfunction "1_1") (pintype "passive"))
    )
    (net (code "40") (name "Net-(LED4-PadC)") (class "Default")
      (node (ref "LED4") (pin "C") (pinfunction "C_C") (pintype "passive"))
      (node (ref "R11") (pin "1") (pinfunction "1_1") (pintype "passive"))
    )
    (net (code "41") (name "Net-(U1-PB6(XTAL1{slash}TOSC1))") (class "Default")
      (node (ref "U1") (pin "7") (pinfunction "PB6(XTAL1/TOSC1)_7") (pintype "bidirectional"))
      (node (ref "Y1") (pin "1") (pinfunction "1_1") (pintype "passive"))
    )
    (net (code "42") (name "Net-(U1-PB7(XTAL2{slash}TOSC2))") (class "Default")
      (node (ref "U1") (pin "8") (pinfunction "PB7(XTAL2/TOSC2)_8") (pintype "bidirectional"))
      (node (ref "Y1") (pin "3") (pinfunction "3_3") (pintype "passive"))
    )
    (net (code "43") (name "Net-(U4-PROG)") (class "Default")
      (node (ref "R13") (pin "1") (pinfunction "1_1") (pintype "passive"))
      (node (ref "U4") (pin "5") (pinfunction "PROG_5") (pintype "input"))
    )
    (net (code "44") (name "Net-(U4-STAT)") (class "Default")
      (node (ref "R12") (pin "1") (pinfunction "1_1") (pintype "passive"))
      (node (ref "U4") (pin "1") (pinfunction "STAT_1") (pintype "output"))
    )
    (net (code "45") (name "RST") (class "Default")
      (node (ref "C4") (pin "2") (pinfunction "2_2") (pintype "passive"))
      (node (ref "PP-RST") (pin "P$1") (pinfunction "1_P$1") (pintype "bidirectional"))
      (node (ref "R2") (pin "1") (pinfunction "1_1") (pintype "passive"))
      (node (ref "S4") (pin "3") (pinfunction "2_3") (pintype "passive"))
      (node (ref "U1") (pin "29") (pinfunction "PC6(/RESET)_29") (pintype "bidirectional"))
    )
    (net (code "46") (name "RXI") (class "Default")
      (node (ref "JP2") (pin "3") (pinfunction "TXO_3") (pintype "passive"))
      (node (ref "TP-RX") (pin "P$1") (pinfunction "1_P$1") (pintype "bidirectional"))
      (node (ref "U1") (pin "30") (pinfunction "PD0(RXD)_30") (pintype "bidirectional"))
    )
    (net (code "47") (name "SINK1") (class "Default")
      (node (ref "S2") (pin "4") (pinfunction "6_4") (pintype "bidirectional"))
    )
    (net (code "48") (name "SINK2") (class "Default")
      (node (ref "S2") (pin "1") (pinfunction "3_1") (pintype "bidirectional"))
    )
    (net (code "49") (name "TXO") (class "Default")
      (node (ref "JP2") (pin "2") (pinfunction "RXI_2") (pintype "passive"))
      (node (ref "TP-TX") (pin "P$1") (pinfunction "1_P$1") (pintype "bidirectional"))
      (node (ref "U1") (pin "31") (pinfunction "PD1(TXD)_31") (pintype "bidirectional"))
    )
    (net (code "50") (name "VBATT") (class "Default")
      (node (ref "C10") (pin "1") (pinfunction "1_1") (pintype "passive"))
      (node (ref "JP1") (pin "2") (pinfunction "2_2") (pintype "passive"))
      (node (ref "S1") (pin "1") (pinfunction "3_1") (pintype "bidirectional"))
      (node (ref "S1") (pin "4") (pinfunction "6_4") (pintype "bidirectional"))
      (node (ref "U4") (pin "3") (pinfunction "VBAT_3") (pintype "power_in"))
    )
    (net (code "51") (name "VCC") (class "Default")
      (node (ref "C1") (pin "1") (pinfunction "1_1") (pintype "passive"))
      (node (ref "C2") (pin "A") (pinfunction "+_A") (pintype "passive"))
      (node (ref "C3") (pin "1") (pinfunction "1_1") (pintype "passive"))
      (node (ref "C5") (pin "1") (pinfunction "1_1") (pintype "passive"))
      (node (ref "D2") (pin "A") (pinfunction "A_A") (pintype "bidirectional"))
      (node (ref "LIGHT+") (pin "1") (pinfunction "1_1") (pintype "bidirectional"))
      (node (ref "R2") (pin "2") (pinfunction "2_2") (pintype "passive"))
      (node (ref "S1") (pin "2") (pinfunction "2_2") (pintype "bidirectional"))
      (node (ref "S1") (pin "5") (pinfunction "5_5") (pintype "bidirectional"))
      (node (ref "TEMP+") (pin "1") (pinfunction "1_1") (pintype "bidirectional"))
      (node (ref "U$2") (pin "P$2") (pinfunction "P$2_P$2") (pintype "bidirectional"))
      (node (ref "U$20") (pin "P$4") (pinfunction "P$4_P$4") (pintype "bidirectional"))
      (node (ref "U$25") (pin "1") (pinfunction "1_1") (pintype "bidirectional"))
      (node (ref "U$33") (pin "P$2") (pinfunction "P$2_P$2") (pintype "bidirectional"))
      (node (ref "U$45") (pin "1") (pinfunction "1_1") (pintype "bidirectional"))
      (node (ref "U$8") (pin "P$4") (pinfunction "P$4_P$4") (pintype "bidirectional"))
      (node (ref "U1") (pin "18") (pinfunction "AVCC_18") (pintype "bidirectional"))
      (node (ref "U1") (pin "20") (pinfunction "AREF_20") (pintype "bidirectional"))
      (node (ref "U1") (pin "4") (pinfunction "VCC_4") (pintype "bidirectional"))
      (node (ref "U1") (pin "6") (pinfunction "VCC_6") (pintype "bidirectional"))
      (node (ref "U2") (pin "1") (pinfunction "VCC_1") (pintype "bidirectional"))
      (node (ref "U3") (pin "COLLECTOR") (pinfunction "C1_COLLECTOR") (pintype "passive"))
    )
    (net (code "52") (name "unconnected-(S3-Pad1)") (class "Default")
      (node (ref "S3") (pin "1") (pinfunction "1_1") (pintype "passive"))
    )
    (net (code "53") (name "unconnected-(S3-Pad3)") (class "Default")
      (node (ref "S3") (pin "3") (pinfunction "3_3") (pintype "passive"))
    )
    (net (code "54") (name "unconnected-(U$3-PadP$2)") (class "Default")
      (node (ref "U$3") (pin "P$2") (pinfunction "P$2_P$2") (pintype "bidirectional"))
    )
    (net (code "55") (name "unconnected-(U$6-PadP$2)") (class "Default")
      (node (ref "U$6") (pin "P$2") (pinfunction "P$2_P$2") (pintype "bidirectional"))
    )
    (net (code "56") (name "unconnected-(U$7-PadP$2)") (class "Default")
      (node (ref "U$7") (pin "P$2") (pinfunction "P$2_P$2") (pintype "bidirectional"))
    )
    (net (code "57") (name "unconnected-(U$8-PadP$6)") (class "Default")
      (node (ref "U$8") (pin "P$6") (pinfunction "P$6_P$6") (pintype "bidirectional"))
    )
    (net (code "58") (name "unconnected-(U$47-PadP$2)") (class "Default")
      (node (ref "U$47") (pin "P$2") (pinfunction "P$2_P$2") (pintype "bidirectional"))
    )
    (net (code "59") (name "unconnected-(U1-ADC7-Pad22)") (class "Default")
      (node (ref "U1") (pin "22") (pinfunction "ADC7_22") (pintype "bidirectional"))
    )
    (net (code "60") (name "unconnected-(U1-PB0(ICP)-Pad12)") (class "Default")
      (node (ref "U1") (pin "12") (pinfunction "PB0(ICP)_12") (pintype "bidirectional"))
    )
    (net (code "61") (name "unconnected-(U1-PC0(ADC0)-Pad23)") (class "Default")
      (node (ref "U1") (pin "23") (pinfunction "PC0(ADC0)_23") (pintype "bidirectional"))
    )
    (net (code "62") (name "unconnected-(U1-PD4(XCK{slash}T0)-Pad2)") (class "Default")
      (node (ref "U1") (pin "2") (pinfunction "PD4(XCK/T0)_2") (pintype "bidirectional"))
    )
  )
)
